# Sensor.net
KiCad netlist of a schematic drawn in Altium Designer
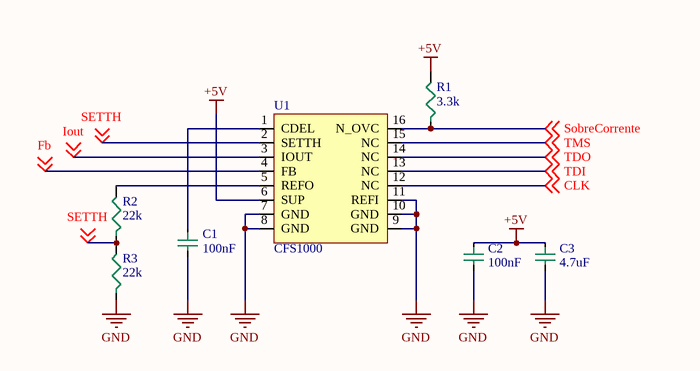
[diagram p0: Sensor.SchDoc]

(export (version "E")
  (design (tool "Eeschema 10.0.6"))
  (components
    (comp (ref "C1")
      (value "100nF")
      (footprint "0603C")
      (description "Capacitor SMD 0603")
      (fields (field (name "Comment") "0603"))
      (libsource (lib "RLC_Integrated_Library") (part "Capacitor SMD 0603"))
    )
    (comp (ref "C2")
      (value "100nF")
      (footprint "0603C")
      (description "Capacitor SMD 0603")
      (fields (field (name "Comment") "0603"))
      (libsource (lib "RLC_Integrated_Library") (part "Capacitor SMD 0603"))
    )
    (comp (ref "C3")
      (value "4.7uF")
      (footprint "0603C")
      (description "Capacitor SMD 0603")
      (fields (field (name "Comment") "0603"))
      (libsource (lib "RLC_Integrated_Library") (part "Capacitor SMD 0603"))
    )
    (comp (ref "R1")
      (value "3.3k")
      (footprint "0603")
      (description "Resistor SMD 0603 1/10 W")
      (fields (field (name "Comment") "0603"))
      (libsource (lib "RLC_Integrated_Library") (part "Resistor SMD 0603 1/10 W"))
    )
    (comp (ref "R2")
      (value "22k")
      (footprint "0603")
      (description "Resistor SMD 0603 1/10 W")
      (fields (field (name "Comment") "0603"))
      (libsource (lib "RLC_Integrated_Library") (part "Resistor SMD 0603 1/10 W"))
    )
    (comp (ref "R3")
      (value "22k")
      (footprint "0603")
      (description "Resistor SMD 0603 1/10 W")
      (fields (field (name "Comment") "0603"))
      (libsource (lib "RLC_Integrated_Library") (part "Resistor SMD 0603 1/10 W"))
    )
    (comp (ref "U1")
      (value "CFS1000")
      (footprint "SO16w")
      (description "CFS1000 magneto resistive current sensor")
      (libsource (lib "CI_Integrated_Library") (part "CI CFS1000"))
    )
  )
  (nets
    (net (code "1") (name "+5V") (class "Default")
      (node (ref "C2") (pin "1") (pinfunction "1_1") (pintype "passive"))
      (node (ref "C3") (pin "1") (pinfunction "1_1") (pintype "passive"))
      (node (ref "R1") (pin "2") (pinfunction "2_2") (pintype "passive"))
      (node (ref "U1") (pin "6") (pinfunction "SUP_6") (pintype "passive"))
    )
    (net (code "2") (name "CLK") (class "Default")
      (node (ref "U1") (pin "12") (pinfunction "NC_12") (pintype "passive"))
    )
    (net (code "3") (name "Fb") (class "Default")
      (node (ref "U1") (pin "4") (pinfunction "FB_4") (pintype "passive"))
    )
    (net (code "4") (name "GND") (class "Default")
      (node (ref "C1") (pin "2") (pinfunction "2_2") (pintype "passive"))
      (node (ref "C2") (pin "2") (pinfunction "2_2") (pintype "passive"))
      (node (ref "C3") (pin "2") (pinfunction "2_2") (pintype "passive"))
      (node (ref "R3") (pin "1") (pinfunction "1_1") (pintype "passive"))
      (node (ref "U1") (pin "10") (pinfunction "GND_10") (pintype "passive"))
      (node (ref "U1") (pin "11") (pinfunction "REFI_11") (pintype "passive"))
      (node (ref "U1") (pin "7") (pinfunction "GND_7") (pintype "passive"))
      (node (ref "U1") (pin "8") (pinfunction "GND_8") (pintype "passive"))
      (node (ref "U1") (pin "9") (pinfunction "GND_9") (pintype "passive"))
    )
    (net (code "5") (name "Iout") (class "Default")
      (node (ref "U1") (pin "3") (pinfunction "IOUT_3") (pintype "passive"))
    )
    (net (code "6") (name "Net-(U1-CDEL)") (class "Default")
      (node (ref "C1") (pin "1") (pinfunction "1_1") (pintype "passive"))
      (node (ref "U1") (pin "1") (pinfunction "CDEL_1") (pintype "passive"))
    )
    (net (code "7") (name "Net-(U1-REFO)") (class "Default")
      (node (ref "R2") (pin "2") (pinfunction "2_2") (pintype "passive"))
      (node (ref "U1") (pin "5") (pinfunction "REFO_5") (pintype "passive"))
    )
    (net (code "8") (name "SETTH") (class "Default")
      (node (ref "R2") (pin "1") (pinfunction "1_1") (pintype "passive"))
      (node (ref "R3") (pin "2") (pinfunction "2_2") (pintype "passive"))
      (node (ref "U1") (pin "2") (pinfunction "SETTH_2") (pintype "passive"))
    )
    (net (code "9") (name "SobreCorrente") (class "Default")
      (node (ref "R1") (pin "1") (pinfunction "1_1") (pintype "passive"))
      (node (ref "U1") (pin "16") (pinfunction "N_OVC_16") (pintype "passive"))
    )
    (net (code "10") (name "TDI") (class "Default")
      (node (ref "U1") (pin "13") (pinfunction "NC_13") (pintype "passive"))
    )
    (net (code "11") (name "TDO") (class "Default")
      (node (ref "U1") (pin "14") (pinfunction "NC_14") (pintype "passive"))
    )
    (net (code "12") (name "TMS") (class "Default")
      (node (ref "U1") (pin "15") (pinfunction "NC_15") (pintype "passive"))
    )
  )
)
